# clap.net
KiCad netlist of a schematic drawn in EAGLE
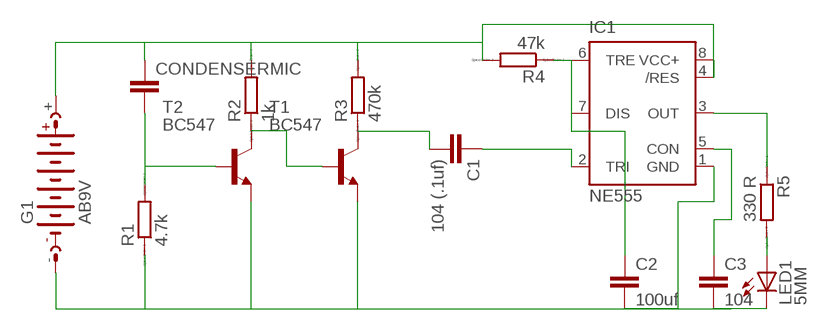
[diagram p0: schematic, sheet 1]

(export (version "E")
  (design (tool "Eeschema 10.0.6"))
  (components
    (comp (ref "C1")
      (value "104 (.1uf)")
      (footprint "eagle-import:C2.5-4")
      (libsource (lib "eagle-import") (part "C2.5/4"))
    )
    (comp (ref "C2")
      (value "100uf")
      (footprint "eagle-import:C2.5-5")
      (libsource (lib "eagle-import") (part "C2.5/5"))
    )
    (comp (ref "C3")
      (value "104")
      (footprint "eagle-import:C2.5-2")
      (libsource (lib "eagle-import") (part "C2.5/2"))
    )
    (comp (ref "CONDENSERMIC")
      (value "C2.5/4")
      (footprint "eagle-import:C2.5-4")
      (libsource (lib "eagle-import") (part "C2.5/4"))
    )
    (comp (ref "G1")
      (value "AB9V")
      (footprint "eagle-import:AB9V")
      (libsource (lib "eagle-import") (part "AB9V"))
    )
    (comp (ref "IC1")
      (value "NE555")
      (footprint "eagle-import:DIL-08")
      (fields (field (name "MF") "Arrow Electronics") (field (name "MPN") "NE555N"))
      (libsource (lib "eagle-import") (part "NE555"))
    )
    (comp (ref "LED1")
      (value "5MM")
      (footprint "eagle-import:LED5MM")
      (libsource (lib "eagle-import") (part "LED5MM"))
    )
    (comp (ref "R1")
      (value "4.7k")
      (footprint "eagle-import:0207_10")
      (libsource (lib "eagle-import") (part "R0207/10"))
    )
    (comp (ref "R2")
      (value "1k")
      (footprint "eagle-import:0207_10")
      (libsource (lib "eagle-import") (part "R0207/10"))
    )
    (comp (ref "R3")
      (value "470k")
      (footprint "eagle-import:0207_10")
      (libsource (lib "eagle-import") (part "R0207/10"))
    )
    (comp (ref "R4")
      (value "47k")
      (footprint "eagle-import:0207_10")
      (libsource (lib "eagle-import") (part "R0207/10"))
    )
    (comp (ref "R5")
      (value "330 R")
      (footprint "eagle-import:0207_10")
      (libsource (lib "eagle-import") (part "R0207/10"))
    )
    (comp (ref "T1")
      (value "BC547")
      (footprint "eagle-import:TO92")
      (libsource (lib "eagle-import") (part "BC547"))
    )
    (comp (ref "T2")
      (value "BC547")
      (footprint "eagle-import:TO92")
      (libsource (lib "eagle-import") (part "BC547"))
    )
  )
  (nets
    (net (code "1") (name "Net-(IC1-CON)") (class "Default")
      (node (ref "C3") (pin "1") (pinfunction "1_1") (pintype "passive"))
      (node (ref "IC1") (pin "5") (pinfunction "CON_5") (pintype "input"))
    )
    (net (code "2") (name "Net-(IC1-DIS)") (class "Default")
      (node (ref "C2") (pin "1") (pinfunction "1_1") (pintype "passive"))
      (node (ref "IC1") (pin "6") (pinfunction "TRE_6") (pintype "input"))
      (node (ref "IC1") (pin "7") (pinfunction "DIS_7") (pintype "input"))
      (node (ref "R4") (pin "1") (pinfunction "1_1") (pintype "passive"))
    )
    (net (code "3") (name "Net-(IC1-GND)") (class "Default")
      (node (ref "C2") (pin "2") (pinfunction "2_2") (pintype "passive"))
      (node (ref "C3") (pin "2") (pinfunction "2_2") (pintype "passive"))
      (node (ref "G1") (pin "-") (pinfunction "-_-") (pintype "passive"))
      (node (ref "IC1") (pin "1") (pinfunction "GND_1") (pintype "power_in"))
      (node (ref "LED1") (pin "K") (pinfunction "C_K") (pintype "passive"))
      (node (ref "R1") (pin "1") (pinfunction "1_1") (pintype "passive"))
      (node (ref "T1") (pin "1") (pinfunction "E_1") (pintype "passive"))
      (node (ref "T2") (pin "1") (pinfunction "E_1") (pintype "passive"))
    )
    (net (code "4") (name "Net-(IC1-OUT)") (class "Default")
      (node (ref "IC1") (pin "3") (pinfunction "OUT_3") (pintype "output"))
      (node (ref "R5") (pin "1") (pinfunction "1_1") (pintype "passive"))
    )
    (net (code "5") (name "Net-(IC1-TRI)") (class "Default")
      (node (ref "C1") (pin "1") (pinfunction "1_1") (pintype "passive"))
      (node (ref "IC1") (pin "2") (pinfunction "TRI_2") (pintype "input"))
    )
    (net (code "6") (name "Net-(IC1-VCC+)") (class "Default")
      (node (ref "CONDENSERMIC") (pin "1") (pinfunction "1_1") (pintype "passive"))
      (node (ref "G1") (pin "+") (pinfunction "+_+") (pintype "passive"))
      (node (ref "IC1") (pin "4") (pinfunction "/RES_4") (pintype "input"))
      (node (ref "IC1") (pin "8") (pinfunction "VCC+_8") (pintype "power_in"))
      (node (ref "R2") (pin "2") (pinfunction "2_2") (pintype "passive"))
      (node (ref "R3") (pin "2") (pinfunction "2_2") (pintype "passive"))
      (node (ref "R4") (pin "2") (pinfunction "2_2") (pintype "passive"))
    )
    (net (code "7") (name "Net-(LED1-PadA)") (class "Default")
      (node (ref "LED1") (pin "A") (pinfunction "A_A") (pintype "passive"))
      (node (ref "R5") (pin "2") (pinfunction "2_2") (pintype "passive"))
    )
    (net (code "8") (name "Net-(T1-B)") (class "Default")
      (node (ref "R2") (pin "1") (pinfunction "1_1") (pintype "passive"))
      (node (ref "T1") (pin "2") (pinfunction "B_2") (pintype "passive"))
      (node (ref "T2") (pin "3") (pinfunction "C_3") (pintype "passive"))
    )
    (net (code "9") (name "Net-(T1-C)") (class "Default")
      (node (ref "C1") (pin "2") (pinfunction "2_2") (pintype "passive"))
      (node (ref "R3") (pin "1") (pinfunction "1_1") (pintype "passive"))
      (node (ref "T1") (pin "3") (pinfunction "C_3") (pintype "passive"))
    )
    (net (code "10") (name "Net-(T2-B)") (class "Default")
      (node (ref "CONDENSERMIC") (pin "2") (pinfunction "2_2") (pintype "passive"))
      (node (ref "R1") (pin "2") (pinfunction "2_2") (pintype "passive"))
      (node (ref "T2") (pin "2") (pinfunction "B_2") (pintype "passive"))
    )
  )
)
